# NumatoConnection.net
KiCad netlist of a schematic drawn in Altium Designer
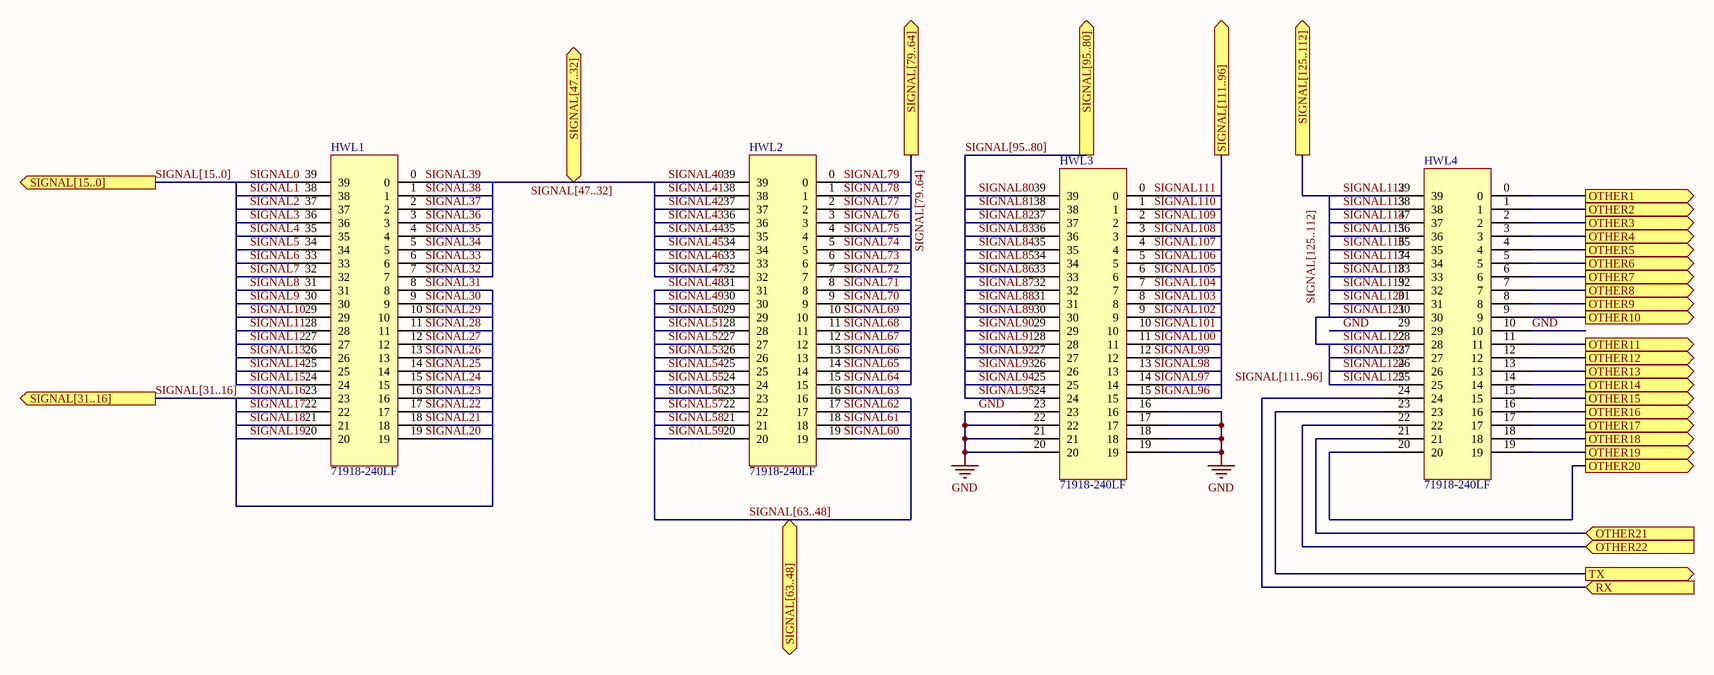
[diagram p0: NumatoConnection.SchDoc]

(export (version "E")
  (design (tool "Eeschema 10.0.6"))
  (components
    (comp (ref "HWL1")
      (value "71918-240LF")
      (footprint "HWL_FP")
      (description "CONN HEADER 40POS DUAL VERT PCB")
      (fields (field (name "MANUFACTURER") "FCI") (field (name "MANUFACTURER PART NUMBER") "71918-240LF"))
      (libsource (lib "NumatoShield") (part "71918-240LF"))
    )
    (comp (ref "HWL2")
      (value "71918-240LF")
      (footprint "HWL_FP")
      (description "CONN HEADER 40POS DUAL VERT PCB")
      (fields (field (name "MANUFACTURER") "FCI") (field (name "MANUFACTURER PART NUMBER") "71918-240LF"))
      (libsource (lib "NumatoShield") (part "71918-240LF"))
    )
    (comp (ref "HWL3")
      (value "71918-240LF")
      (footprint "HWL_FP")
      (description "CONN HEADER 40POS DUAL VERT PCB")
      (fields (field (name "MANUFACTURER") "FCI") (field (name "MANUFACTURER PART NUMBER") "71918-240LF"))
      (libsource (lib "NumatoShield") (part "71918-240LF"))
    )
    (comp (ref "HWL4")
      (value "71918-240LF")
      (footprint "HWL_FP")
      (description "CONN HEADER 40POS DUAL VERT PCB")
      (fields (field (name "MANUFACTURER") "FCI") (field (name "MANUFACTURER PART NUMBER") "71918-240LF"))
      (libsource (lib "NumatoShield") (part "71918-240LF"))
    )
  )
  (nets
    (net (code "2") (name "/OTHER1") (class "Default")
      (node (ref "HWL4") (pin "0") (pinfunction "0_0") (pintype "passive"))
    )
    (net (code "3") (name "/OTHER2") (class "Default")
      (node (ref "HWL4") (pin "1") (pinfunction "1_1") (pintype "passive"))
    )
    (net (code "4") (name "/OTHER3") (class "Default")
      (node (ref "HWL4") (pin "2") (pinfunction "2_2") (pintype "passive"))
    )
    (net (code "5") (name "/OTHER4") (class "Default")
      (node (ref "HWL4") (pin "3") (pinfunction "3_3") (pintype "passive"))
    )
    (net (code "6") (name "/OTHER5") (class "Default")
      (node (ref "HWL4") (pin "4") (pinfunction "4_4") (pintype "passive"))
    )
    (net (code "7") (name "/OTHER6") (class "Default")
      (node (ref "HWL4") (pin "5") (pinfunction "5_5") (pintype "passive"))
    )
    (net (code "8") (name "/OTHER7") (class "Default")
      (node (ref "HWL4") (pin "6") (pinfunction "6_6") (pintype "passive"))
    )
    (net (code "9") (name "/OTHER8") (class "Default")
      (node (ref "HWL4") (pin "7") (pinfunction "7_7") (pintype "passive"))
    )
    (net (code "10") (name "/OTHER9") (class "Default")
      (node (ref "HWL4") (pin "8") (pinfunction "8_8") (pintype "passive"))
    )
    (net (code "11") (name "/OTHER10") (class "Default")
      (node (ref "HWL4") (pin "9") (pinfunction "9_9") (pintype "passive"))
    )
    (net (code "12") (name "/OTHER11") (class "Default")
      (node (ref "HWL4") (pin "11") (pinfunction "11_11") (pintype "passive"))
    )
    (net (code "13") (name "/OTHER12") (class "Default")
      (node (ref "HWL4") (pin "12") (pinfunction "12_12") (pintype "passive"))
    )
    (net (code "14") (name "/OTHER13") (class "Default")
      (node (ref "HWL4") (pin "13") (pinfunction "13_13") (pintype "passive"))
    )
    (net (code "15") (name "/OTHER14") (class "Default")
      (node (ref "HWL4") (pin "14") (pinfunction "14_14") (pintype "passive"))
    )
    (net (code "16") (name "/OTHER15") (class "Default")
      (node (ref "HWL4") (pin "15") (pinfunction "15_15") (pintype "passive"))
    )
    (net (code "17") (name "/OTHER16") (class "Default")
      (node (ref "HWL4") (pin "16") (pinfunction "16_16") (pintype "passive"))
    )
    (net (code "18") (name "/OTHER17") (class "Default")
      (node (ref "HWL4") (pin "17") (pinfunction "17_17") (pintype "passive"))
    )
    (net (code "19") (name "/OTHER18") (class "Default")
      (node (ref "HWL4") (pin "18") (pinfunction "18_18") (pintype "passive"))
    )
    (net (code "20") (name "/OTHER19") (class "Default")
      (node (ref "HWL4") (pin "19") (pinfunction "19_19") (pintype "passive"))
    )
    (net (code "21") (name "/OTHER20") (class "Default")
      (node (ref "HWL4") (pin "20") (pinfunction "20_20") (pintype "passive"))
    )
    (net (code "22") (name "/OTHER21") (class "Default")
      (node (ref "HWL4") (pin "21") (pinfunction "21_21") (pintype "passive"))
    )
    (net (code "23") (name "/OTHER22") (class "Default")
      (node (ref "HWL4") (pin "22") (pinfunction "22_22") (pintype "passive"))
    )
    (net (code "24") (name "/RX") (class "Default")
      (node (ref "HWL4") (pin "24") (pinfunction "24_24") (pintype "passive"))
    )
    (net (code "25") (name "/SIGNAL0") (class "Default")
      (node (ref "HWL1") (pin "39") (pinfunction "39_39") (pintype "passive"))
    )
    (net (code "26") (name "/SIGNAL1") (class "Default")
      (node (ref "HWL1") (pin "38") (pinfunction "38_38") (pintype "passive"))
    )
    (net (code "27") (name "/SIGNAL2") (class "Default")
      (node (ref "HWL1") (pin "37") (pinfunction "37_37") (pintype "passive"))
    )
    (net (code "28") (name "/SIGNAL3") (class "Default")
      (node (ref "HWL1") (pin "36") (pinfunction "36_36") (pintype "passive"))
    )
    (net (code "29") (name "/SIGNAL4") (class "Default")
      (node (ref "HWL1") (pin "35") (pinfunction "35_35") (pintype "passive"))
    )
    (net (code "30") (name "/SIGNAL5") (class "Default")
      (node (ref "HWL1") (pin "34") (pinfunction "34_34") (pintype "passive"))
    )
    (net (code "31") (name "/SIGNAL6") (class "Default")
      (node (ref "HWL1") (pin "33") (pinfunction "33_33") (pintype "passive"))
    )
    (net (code "32") (name "/SIGNAL7") (class "Default")
      (node (ref "HWL1") (pin "32") (pinfunction "32_32") (pintype "passive"))
    )
    (net (code "33") (name "/SIGNAL8") (class "Default")
      (node (ref "HWL1") (pin "31") (pinfunction "31_31") (pintype "passive"))
    )
    (net (code "34") (name "/SIGNAL9") (class "Default")
      (node (ref "HWL1") (pin "30") (pinfunction "30_30") (pintype "passive"))
    )
    (net (code "35") (name "/SIGNAL10") (class "Default")
      (node (ref "HWL1") (pin "29") (pinfunction "29_29") (pintype "passive"))
    )
    (net (code "36") (name "/SIGNAL11") (class "Default")
      (node (ref "HWL1") (pin "28") (pinfunction "28_28") (pintype "passive"))
    )
    (net (code "37") (name "/SIGNAL12") (class "Default")
      (node (ref "HWL1") (pin "27") (pinfunction "27_27") (pintype "passive"))
    )
    (net (code "38") (name "/SIGNAL12~{3}") (class "Default")
      (node (ref "HWL4") (pin "27") (pinfunction "27_27") (pintype "passive"))
    )
    (net (code "39") (name "/SIGNAL13") (class "Default")
      (node (ref "HWL1") (pin "26") (pinfunction "26_26") (pintype "passive"))
    )
    (net (code "40") (name "/SIGNAL14") (class "Default")
      (node (ref "HWL1") (pin "25") (pinfunction "25_25") (pintype "passive"))
    )
    (net (code "41") (name "/SIGNAL15") (class "Default")
      (node (ref "HWL1") (pin "24") (pinfunction "24_24") (pintype "passive"))
    )
    (net (code "42") (name "/SIGNAL16") (class "Default")
      (node (ref "HWL1") (pin "23") (pinfunction "23_23") (pintype "passive"))
    )
    (net (code "43") (name "/SIGNAL17") (class "Default")
      (node (ref "HWL1") (pin "22") (pinfunction "22_22") (pintype "passive"))
    )
    (net (code "44") (name "/SIGNAL18") (class "Default")
      (node (ref "HWL1") (pin "21") (pinfunction "21_21") (pintype "passive"))
    )
    (net (code "45") (name "/SIGNAL19") (class "Default")
      (node (ref "HWL1") (pin "20") (pinfunction "20_20") (pintype "passive"))
    )
    (net (code "66") (name "/SIGNAL40") (class "Default")
      (node (ref "HWL2") (pin "39") (pinfunction "39_39") (pintype "passive"))
    )
    (net (code "67") (name "/SIGNAL41") (class "Default")
      (node (ref "HWL2") (pin "38") (pinfunction "38_38") (pintype "passive"))
    )
    (net (code "68") (name "/SIGNAL42") (class "Default")
      (node (ref "HWL2") (pin "37") (pinfunction "37_37") (pintype "passive"))
    )
    (net (code "69") (name "/SIGNAL43") (class "Default")
      (node (ref "HWL2") (pin "36") (pinfunction "36_36") (pintype "passive"))
    )
    (net (code "70") (name "/SIGNAL44") (class "Default")
      (node (ref "HWL2") (pin "35") (pinfunction "35_35") (pintype "passive"))
    )
    (net (code "71") (name "/SIGNAL45") (class "Default")
      (node (ref "HWL2") (pin "34") (pinfunction "34_34") (pintype "passive"))
    )
    (net (code "72") (name "/SIGNAL46") (class "Default")
      (node (ref "HWL2") (pin "33") (pinfunction "33_33") (pintype "passive"))
    )
    (net (code "73") (name "/SIGNAL47") (class "Default")
      (node (ref "HWL2") (pin "32") (pinfunction "32_32") (pintype "passive"))
    )
    (net (code "74") (name "/SIGNAL48") (class "Default")
      (node (ref "HWL2") (pin "31") (pinfunction "31_31") (pintype "passive"))
    )
    (net (code "75") (name "/SIGNAL49") (class "Default")
      (node (ref "HWL2") (pin "30") (pinfunction "30_30") (pintype "passive"))
    )
    (net (code "76") (name "/SIGNAL50") (class "Default")
      (node (ref "HWL2") (pin "29") (pinfunction "29_29") (pintype "passive"))
    )
    (net (code "77") (name "/SIGNAL51") (class "Default")
      (node (ref "HWL2") (pin "28") (pinfunction "28_28") (pintype "passive"))
    )
    (net (code "78") (name "/SIGNAL52") (class "Default")
      (node (ref "HWL2") (pin "27") (pinfunction "27_27") (pintype "passive"))
    )
    (net (code "79") (name "/SIGNAL53") (class "Default")
      (node (ref "HWL2") (pin "26") (pinfunction "26_26") (pintype "passive"))
    )
    (net (code "80") (name "/SIGNAL54") (class "Default")
      (node (ref "HWL2") (pin "25") (pinfunction "25_25") (pintype "passive"))
    )
    (net (code "81") (name "/SIGNAL55") (class "Default")
      (node (ref "HWL2") (pin "24") (pinfunction "24_24") (pintype "passive"))
    )
    (net (code "82") (name "/SIGNAL56") (class "Default")
      (node (ref "HWL2") (pin "23") (pinfunction "23_23") (pintype "passive"))
    )
    (net (code "83") (name "/SIGNAL57") (class "Default")
      (node (ref "HWL2") (pin "22") (pinfunction "22_22") (pintype "passive"))
    )
    (net (code "84") (name "/SIGNAL58") (class "Default")
      (node (ref "HWL2") (pin "21") (pinfunction "21_21") (pintype "passive"))
    )
    (net (code "85") (name "/SIGNAL59") (class "Default")
      (node (ref "HWL2") (pin "20") (pinfunction "20_20") (pintype "passive"))
    )
    (net (code "106") (name "/SIGNAL80") (class "Default")
      (node (ref "HWL3") (pin "39") (pinfunction "39_39") (pintype "passive"))
    )
    (net (code "107") (name "/SIGNAL81") (class "Default")
      (node (ref "HWL3") (pin "38") (pinfunction "38_38") (pintype "passive"))
    )
    (net (code "108") (name "/SIGNAL82") (class "Default")
      (node (ref "HWL3") (pin "37") (pinfunction "37_37") (pintype "passive"))
    )
    (net (code "109") (name "/SIGNAL83") (class "Default")
      (node (ref "HWL3") (pin "36") (pinfunction "36_36") (pintype "passive"))
    )
    (net (code "110") (name "/SIGNAL84") (class "Default")
      (node (ref "HWL3") (pin "35") (pinfunction "35_35") (pintype "passive"))
    )
    (net (code "111") (name "/SIGNAL85") (class "Default")
      (node (ref "HWL3") (pin "34") (pinfunction "34_34") (pintype "passive"))
    )
    (net (code "112") (name "/SIGNAL86") (class "Default")
      (node (ref "HWL3") (pin "33") (pinfunction "33_33") (pintype "passive"))
    )
    (net (code "113") (name "/SIGNAL87") (class "Default")
      (node (ref "HWL3") (pin "32") (pinfunction "32_32") (pintype "passive"))
    )
    (net (code "114") (name "/SIGNAL88") (class "Default")
      (node (ref "HWL3") (pin "31") (pinfunction "31_31") (pintype "passive"))
    )
    (net (code "115") (name "/SIGNAL89") (class "Default")
      (node (ref "HWL3") (pin "30") (pinfunction "30_30") (pintype "passive"))
    )
    (net (code "116") (name "/SIGNAL90") (class "Default")
      (node (ref "HWL3") (pin "29") (pinfunction "29_29") (pintype "passive"))
    )
    (net (code "117") (name "/SIGNAL91") (class "Default")
      (node (ref "HWL3") (pin "28") (pinfunction "28_28") (pintype "passive"))
    )
    (net (code "118") (name "/SIGNAL92") (class "Default")
      (node (ref "HWL3") (pin "27") (pinfunction "27_27") (pintype "passive"))
    )
    (net (code "119") (name "/SIGNAL93") (class "Default")
      (node (ref "HWL3") (pin "26") (pinfunction "26_26") (pintype "passive"))
    )
    (net (code "120") (name "/SIGNAL94") (class "Default")
      (node (ref "HWL3") (pin "25") (pinfunction "25_25") (pintype "passive"))
    )
    (net (code "121") (name "/SIGNAL95") (class "Default")
      (node (ref "HWL3") (pin "24") (pinfunction "24_24") (pintype "passive"))
    )
    (net (code "138") (name "/SIGNAL112") (class "Default")
      (node (ref "HWL4") (pin "39") (pinfunction "39_39") (pintype "passive"))
    )
    (net (code "139") (name "/SIGNAL113") (class "Default")
      (node (ref "HWL4") (pin "38") (pinfunction "38_38") (pintype "passive"))
    )
    (net (code "140") (name "/SIGNAL114") (class "Default")
      (node (ref "HWL4") (pin "37") (pinfunction "37_37") (pintype "passive"))
    )
    (net (code "141") (name "/SIGNAL115") (class "Default")
      (node (ref "HWL4") (pin "36") (pinfunction "36_36") (pintype "passive"))
    )
    (net (code "142") (name "/SIGNAL116") (class "Default")
      (node (ref "HWL4") (pin "35") (pinfunction "35_35") (pintype "passive"))
    )
    (net (code "143") (name "/SIGNAL117") (class "Default")
      (node (ref "HWL4") (pin "34") (pinfunction "34_34") (pintype "passive"))
    )
    (net (code "144") (name "/SIGNAL118") (class "Default")
      (node (ref "HWL4") (pin "33") (pinfunction "33_33") (pintype "passive"))
    )
    (net (code "145") (name "/SIGNAL119") (class "Default")
      (node (ref "HWL4") (pin "32") (pinfunction "32_32") (pintype "passive"))
    )
    (net (code "146") (name "/SIGNAL120") (class "Default")
      (node (ref "HWL4") (pin "31") (pinfunction "31_31") (pintype "passive"))
    )
    (net (code "147") (name "/SIGNAL121") (class "Default")
      (node (ref "HWL4") (pin "30") (pinfunction "30_30") (pintype "passive"))
    )
    (net (code "148") (name "/SIGNAL122") (class "Default")
      (node (ref "HWL4") (pin "28") (pinfunction "28_28") (pintype "passive"))
    )
    (net (code "149") (name "/SIGNAL124") (class "Default")
      (node (ref "HWL4") (pin "26") (pinfunction "26_26") (pintype "passive"))
    )
    (net (code "150") (name "/SIGNAL125") (class "Default")
      (node (ref "HWL4") (pin "25") (pinfunction "25_25") (pintype "passive"))
    )
    (net (code "159") (name "/TX") (class "Default")
      (node (ref "HWL4") (pin "23") (pinfunction "23_23") (pintype "passive"))
    )
    (net (code "160") (name "GND") (class "Default")
      (node (ref "HWL3") (pin "16") (pinfunction "16_16") (pintype "passive"))
      (node (ref "HWL3") (pin "17") (pinfunction "17_17") (pintype "passive"))
      (node (ref "HWL3") (pin "18") (pinfunction "18_18") (pintype "passive"))
      (node (ref "HWL3") (pin "19") (pinfunction "19_19") (pintype "passive"))
      (node (ref "HWL3") (pin "20") (pinfunction "20_20") (pintype "passive"))
      (node (ref "HWL3") (pin "21") (pinfunction "21_21") (pintype "passive"))
      (node (ref "HWL3") (pin "22") (pinfunction "22_22") (pintype "passive"))
      (node (ref "HWL3") (pin "23") (pinfunction "23_23") (pintype "passive"))
      (node (ref "HWL4") (pin "10") (pinfunction "10_10") (pintype "passive"))
      (node (ref "HWL4") (pin "29") (pinfunction "29_29") (pintype "passive"))
    )
    (net (code "161") (name "unconnected-(HWL1-Pad0)") (class "Default")
      (node (ref "HWL1") (pin "0") (pinfunction "0_0") (pintype "passive"))
    )
    (net (code "162") (name "unconnected-(HWL1-Pad1)") (class "Default")
      (node (ref "HWL1") (pin "1") (pinfunction "1_1") (pintype "passive"))
    )
    (net (code "163") (name "unconnected-(HWL1-Pad2)") (class "Default")
      (node (ref "HWL1") (pin "2") (pinfunction "2_2") (pintype "passive"))
    )
    (net (code "164") (name "unconnected-(HWL1-Pad3)") (class "Default")
      (node (ref "HWL1") (pin "3") (pinfunction "3_3") (pintype "passive"))
    )
    (net (code "165") (name "unconnected-(HWL1-Pad4)") (class "Default")
      (node (ref "HWL1") (pin "4") (pinfunction "4_4") (pintype "passive"))
    )
    (net (code "166") (name "unconnected-(HWL1-Pad5)") (class "Default")
      (node (ref "HWL1") (pin "5") (pinfunction "5_5") (pintype "passive"))
    )
    (net (code "167") (name "unconnected-(HWL1-Pad6)") (class "Default")
      (node (ref "HWL1") (pin "6") (pinfunction "6_6") (pintype "passive"))
    )
    (net (code "168") (name "unconnected-(HWL1-Pad7)") (class "Default")
      (node (ref "HWL1") (pin "7") (pinfunction "7_7") (pintype "passive"))
    )
    (net (code "169") (name "unconnected-(HWL1-Pad8)") (class "Default")
      (node (ref "HWL1") (pin "8") (pinfunction "8_8") (pintype "passive"))
    )
    (net (code "170") (name "unconnected-(HWL1-Pad9)") (class "Default")
      (node (ref "HWL1") (pin "9") (pinfunction "9_9") (pintype "passive"))
    )
    (net (code "171") (name "unconnected-(HWL1-Pad10)") (class "Default")
      (node (ref "HWL1") (pin "10") (pinfunction "10_10") (pintype "passive"))
    )
    (net (code "172") (name "unconnected-(HWL1-Pad11)") (class "Default")
      (node (ref "HWL1") (pin "11") (pinfunction "11_11") (pintype "passive"))
    )
    (net (code "173") (name "unconnected-(HWL1-Pad12)") (class "Default")
      (node (ref "HWL1") (pin "12") (pinfunction "12_12") (pintype "passive"))
    )
    (net (code "174") (name "unconnected-(HWL1-Pad13)") (class "Default")
      (node (ref "HWL1") (pin "13") (pinfunction "13_13") (pintype "passive"))
    )
    (net (code "175") (name "unconnected-(HWL1-Pad14)") (class "Default")
      (node (ref "HWL1") (pin "14") (pinfunction "14_14") (pintype "passive"))
    )
    (net (code "176") (name "unconnected-(HWL1-Pad15)") (class "Default")
      (node (ref "HWL1") (pin "15") (pinfunction "15_15") (pintype "passive"))
    )
    (net (code "177") (name "unconnected-(HWL1-Pad16)") (class "Default")
      (node (ref "HWL1") (pin "16") (pinfunction "16_16") (pintype "passive"))
    )
    (net (code "178") (name "unconnected-(HWL1-Pad17)") (class "Default")
      (node (ref "HWL1") (pin "17") (pinfunction "17_17") (pintype "passive"))
    )
    (net (code "179") (name "unconnected-(HWL1-Pad18)") (class "Default")
      (node (ref "HWL1") (pin "18") (pinfunction "18_18") (pintype "passive"))
    )
    (net (code "180") (name "unconnected-(HWL1-Pad19)") (class "Default")
      (node (ref "HWL1") (pin "19") (pinfunction "19_19") (pintype "passive"))
    )
    (net (code "181") (name "unconnected-(HWL2-Pad0)") (class "Default")
      (node (ref "HWL2") (pin "0") (pinfunction "0_0") (pintype "passive"))
    )
    (net (code "182") (name "unconnected-(HWL2-Pad1)") (class "Default")
      (node (ref "HWL2") (pin "1") (pinfunction "1_1") (pintype "passive"))
    )
    (net (code "183") (name "unconnected-(HWL2-Pad2)") (class "Default")
      (node (ref "HWL2") (pin "2") (pinfunction "2_2") (pintype "passive"))
    )
    (net (code "184") (name "unconnected-(HWL2-Pad3)") (class "Default")
      (node (ref "HWL2") (pin "3") (pinfunction "3_3") (pintype "passive"))
    )
    (net (code "185") (name "unconnected-(HWL2-Pad4)") (class "Default")
      (node (ref "HWL2") (pin "4") (pinfunction "4_4") (pintype "passive"))
    )
    (net (code "186") (name "unconnected-(HWL2-Pad5)") (class "Default")
      (node (ref "HWL2") (pin "5") (pinfunction "5_5") (pintype "passive"))
    )
    (net (code "187") (name "unconnected-(HWL2-Pad6)") (class "Default")
      (node (ref "HWL2") (pin "6") (pinfunction "6_6") (pintype "passive"))
    )
    (net (code "188") (name "unconnected-(HWL2-Pad7)") (class "Default")
      (node (ref "HWL2") (pin "7") (pinfunction "7_7") (pintype "passive"))
    )
    (net (code "189") (name "unconnected-(HWL2-Pad8)") (class "Default")
      (node (ref "HWL2") (pin "8") (pinfunction "8_8") (pintype "passive"))
    )
    (net (code "190") (name "unconnected-(HWL2-Pad9)") (class "Default")
      (node (ref "HWL2") (pin "9") (pinfunction "9_9") (pintype "passive"))
    )
    (net (code "191") (name "unconnected-(HWL2-Pad10)") (class "Default")
      (node (ref "HWL2") (pin "10") (pinfunction "10_10") (pintype "passive"))
    )
    (net (code "192") (name "unconnected-(HWL2-Pad11)") (class "Default")
      (node (ref "HWL2") (pin "11") (pinfunction "11_11") (pintype "passive"))
    )
    (net (code "193") (name "unconnected-(HWL2-Pad12)") (class "Default")
      (node (ref "HWL2") (pin "12") (pinfunction "12_12") (pintype "passive"))
    )
    (net (code "194") (name "unconnected-(HWL2-Pad13)") (class "Default")
      (node (ref "HWL2") (pin "13") (pinfunction "13_13") (pintype "passive"))
    )
    (net (code "195") (name "unconnected-(HWL2-Pad14)") (class "Default")
      (node (ref "HWL2") (pin "14") (pinfunction "14_14") (pintype "passive"))
    )
    (net (code "196") (name "unconnected-(HWL2-Pad15)") (class "Default")
      (node (ref "HWL2") (pin "15") (pinfunction "15_15") (pintype "passive"))
    )
    (net (code "197") (name "unconnected-(HWL2-Pad16)") (class "Default")
      (node (ref "HWL2") (pin "16") (pinfunction "16_16") (pintype "passive"))
    )
    (net (code "198") (name "unconnected-(HWL2-Pad17)") (class "Default")
      (node (ref "HWL2") (pin "17") (pinfunction "17_17") (pintype "passive"))
    )
    (net (code "199") (name "unconnected-(HWL2-Pad18)") (class "Default")
      (node (ref "HWL2") (pin "18") (pinfunction "18_18") (pintype "passive"))
    )
    (net (code "200") (name "unconnected-(HWL2-Pad19)") (class "Default")
      (node (ref "HWL2") (pin "19") (pinfunction "19_19") (pintype "passive"))
    )
    (net (code "201") (name "unconnected-(HWL3-Pad0)") (class "Default")
      (node (ref "HWL3") (pin "0") (pinfunction "0_0") (pintype "passive"))
    )
    (net (code "202") (name "unconnected-(HWL3-Pad1)") (class "Default")
      (node (ref "HWL3") (pin "1") (pinfunction "1_1") (pintype "passive"))
    )
    (net (code "203") (name "unconnected-(HWL3-Pad2)") (class "Default")
      (node (ref "HWL3") (pin "2") (pinfunction "2_2") (pintype "passive"))
    )
    (net (code "204") (name "unconnected-(HWL3-Pad3)") (class "Default")
      (node (ref "HWL3") (pin "3") (pinfunction "3_3") (pintype "passive"))
    )
    (net (code "205") (name "unconnected-(HWL3-Pad4)") (class "Default")
      (node (ref "HWL3") (pin "4") (pinfunction "4_4") (pintype "passive"))
    )
    (net (code "206") (name "unconnected-(HWL3-Pad5)") (class "Default")
      (node (ref "HWL3") (pin "5") (pinfunction "5_5") (pintype "passive"))
    )
    (net (code "207") (name "unconnected-(HWL3-Pad6)") (class "Default")
      (node (ref "HWL3") (pin "6") (pinfunction "6_6") (pintype "passive"))
    )
    (net (code "208") (name "unconnected-(HWL3-Pad7)") (class "Default")
      (node (ref "HWL3") (pin "7") (pinfunction "7_7") (pintype "passive"))
    )
    (net (code "209") (name "unconnected-(HWL3-Pad8)") (class "Default")
      (node (ref "HWL3") (pin "8") (pinfunction "8_8") (pintype "passive"))
    )
    (net (code "210") (name "unconnected-(HWL3-Pad9)") (class "Default")
      (node (ref "HWL3") (pin "9") (pinfunction "9_9") (pintype "passive"))
    )
    (net (code "211") (name "unconnected-(HWL3-Pad10)") (class "Default")
      (node (ref "HWL3") (pin "10") (pinfunction "10_10") (pintype "passive"))
    )
    (net (code "212") (name "unconnected-(HWL3-Pad11)") (class "Default")
      (node (ref "HWL3") (pin "11") (pinfunction "11_11") (pintype "passive"))
    )
    (net (code "213") (name "unconnected-(HWL3-Pad12)") (class "Default")
      (node (ref "HWL3") (pin "12") (pinfunction "12_12") (pintype "passive"))
    )
    (net (code "214") (name "unconnected-(HWL3-Pad13)") (class "Default")
      (node (ref "HWL3") (pin "13") (pinfunction "13_13") (pintype "passive"))
    )
    (net (code "215") (name "unconnected-(HWL3-Pad14)") (class "Default")
      (node (ref "HWL3") (pin "14") (pinfunction "14_14") (pintype "passive"))
    )
    (net (code "216") (name "unconnected-(HWL3-Pad15)") (class "Default")
      (node (ref "HWL3") (pin "15") (pinfunction "15_15") (pintype "passive"))
    )
  )
)
